# design.net
KiCad netlist of a schematic drawn in Altium Designer
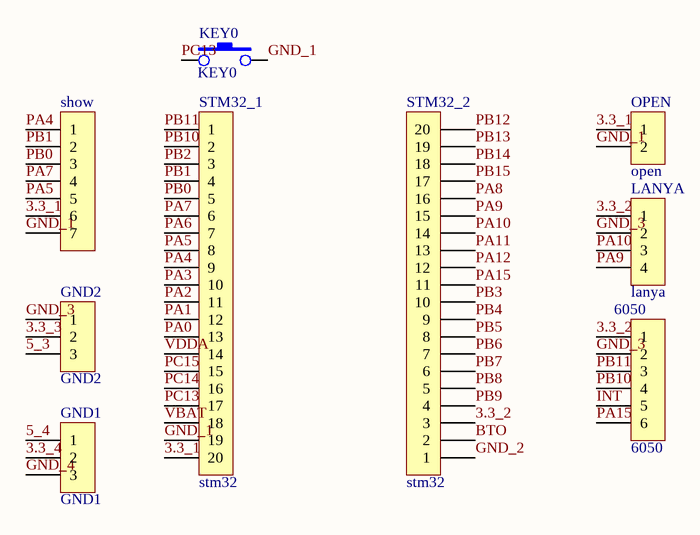
[diagram p0: 遥控器.SchDoc]

(export (version "E")
  (design (tool "Eeschema 10.0.6"))
  (components
    (comp (ref "6050")
      (value "6050")
      (footprint "Fe-HDR1X6/2.54-S")
      (libsource (lib "排母") (part "Female HDR1X6"))
    )
    (comp (ref "GND1")
      (value "GND1")
      (footprint "Fe-HDR1X3/2.54-S")
      (libsource (lib "排母") (part "Female HDR1X3"))
    )
    (comp (ref "GND2")
      (value "GND2")
      (footprint "Fe-HDR1X3/2.54-S")
      (libsource (lib "排母") (part "Female HDR1X3"))
    )
    (comp (ref "KEY0") (value "KEY0") (footprint "DIP-6X6X10") (libsource (lib "轻触开关") (part "KEY")))
    (comp (ref "LANYA")
      (value "lanya")
      (footprint "Fe-HDR1X4/2.54-S")
      (libsource (lib "排母") (part "Female HDR1X4"))
    )
    (comp (ref "OPEN")
      (value "open")
      (footprint "Pin HDR1X2/2.54mm-S")
      (libsource (lib "排针") (part "Pin HDR1X2"))
    )
    (comp (ref "show")
      (value "~")
      (footprint "Fe-HDR1X7/2.54-S")
      (libsource (lib "排母") (part "Female HDR1X7"))
    )
    (comp (ref "STM32_1")
      (value "stm32")
      (footprint "Fe-HDR1X20/2.54-S")
      (libsource (lib "") (part "Female HDR1X20_1"))
    )
    (comp (ref "STM32_2")
      (value "stm32")
      (footprint "Fe-HDR1X20/2.54-S")
      (libsource (lib "排母") (part "Female HDR1X20"))
    )
  )
  (nets
    (net (code "1") (name "/3.3_1") (class "Default")
      (node (ref "OPEN") (pin "1") (pinfunction "1_1") (pintype "passive"))
      (node (ref "STM32_1") (pin "20") (pinfunction "20_20") (pintype "passive"))
      (node (ref "show") (pin "6") (pinfunction "6_6") (pintype "passive"))
    )
    (net (code "2") (name "/3.3_2") (class "Default")
      (node (ref "6050") (pin "1") (pinfunction "1_1") (pintype "passive"))
      (node (ref "LANYA") (pin "1") (pinfunction "1_1") (pintype "passive"))
      (node (ref "STM32_2") (pin "3") (pinfunction "3_3") (pintype "passive"))
    )
    (net (code "3") (name "/3.3_3") (class "Default")
      (node (ref "GND2") (pin "2") (pinfunction "2_2") (pintype "passive"))
    )
    (net (code "4") (name "/3.3_4") (class "Default")
      (node (ref "GND1") (pin "2") (pinfunction "2_2") (pintype "passive"))
    )
    (net (code "5") (name "/5_3") (class "Default")
      (node (ref "GND2") (pin "3") (pinfunction "3_3") (pintype "passive"))
    )
    (net (code "6") (name "/5_4") (class "Default")
      (node (ref "GND1") (pin "1") (pinfunction "1_1") (pintype "passive"))
    )
    (net (code "7") (name "/BTO") (class "Default")
      (node (ref "STM32_2") (pin "2") (pinfunction "2_2") (pintype "passive"))
    )
    (net (code "8") (name "/GND_1") (class "Default")
      (node (ref "KEY0") (pin "3") (pinfunction "3_3") (pintype "passive"))
      (node (ref "OPEN") (pin "2") (pinfunction "2_2") (pintype "passive"))
      (node (ref "STM32_1") (pin "19") (pinfunction "19_19") (pintype "passive"))
      (node (ref "show") (pin "7") (pinfunction "7_7") (pintype "passive"))
    )
    (net (code "9") (name "/GND_2") (class "Default")
      (node (ref "STM32_2") (pin "1") (pinfunction "1_1") (pintype "passive"))
    )
    (net (code "10") (name "/GND_3") (class "Default")
      (node (ref "6050") (pin "2") (pinfunction "2_2") (pintype "passive"))
      (node (ref "GND2") (pin "1") (pinfunction "1_1") (pintype "passive"))
      (node (ref "LANYA") (pin "2") (pinfunction "2_2") (pintype "passive"))
    )
    (net (code "11") (name "/GND_4") (class "Default")
      (node (ref "GND1") (pin "3") (pinfunction "3_3") (pintype "passive"))
    )
    (net (code "12") (name "/INT") (class "Default")
      (node (ref "6050") (pin "5") (pinfunction "5_5") (pintype "passive"))
    )
    (net (code "13") (name "/PA0") (class "Default")
      (node (ref "STM32_1") (pin "13") (pinfunction "13_13") (pintype "passive"))
    )
    (net (code "14") (name "/PA1") (class "Default")
      (node (ref "STM32_1") (pin "12") (pinfunction "12_12") (pintype "passive"))
    )
    (net (code "15") (name "/PA2") (class "Default")
      (node (ref "STM32_1") (pin "11") (pinfunction "11_11") (pintype "passive"))
    )
    (net (code "16") (name "/PA3") (class "Default")
      (node (ref "STM32_1") (pin "10") (pinfunction "10_10") (pintype "passive"))
    )
    (net (code "17") (name "/PA4") (class "Default")
      (node (ref "STM32_1") (pin "9") (pinfunction "9_9") (pintype "passive"))
      (node (ref "show") (pin "1") (pinfunction "1_1") (pintype "passive"))
    )
    (net (code "18") (name "/PA5") (class "Default")
      (node (ref "STM32_1") (pin "8") (pinfunction "8_8") (pintype "passive"))
      (node (ref "show") (pin "5") (pinfunction "5_5") (pintype "passive"))
    )
    (net (code "19") (name "/PA6") (class "Default")
      (node (ref "STM32_1") (pin "7") (pinfunction "7_7") (pintype "passive"))
    )
    (net (code "20") (name "/PA7") (class "Default")
      (node (ref "STM32_1") (pin "6") (pinfunction "6_6") (pintype "passive"))
      (node (ref "show") (pin "4") (pinfunction "4_4") (pintype "passive"))
    )
    (net (code "21") (name "/PA8") (class "Default")
      (node (ref "STM32_2") (pin "16") (pinfunction "16_16") (pintype "passive"))
    )
    (net (code "22") (name "/PA9") (class "Default")
      (node (ref "LANYA") (pin "4") (pinfunction "4_4") (pintype "passive"))
      (node (ref "STM32_2") (pin "15") (pinfunction "15_15") (pintype "passive"))
    )
    (net (code "23") (name "/PA10") (class "Default")
      (node (ref "LANYA") (pin "3") (pinfunction "3_3") (pintype "passive"))
      (node (ref "STM32_2") (pin "14") (pinfunction "14_14") (pintype "passive"))
    )
    (net (code "24") (name "/PA11") (class "Default")
      (node (ref "STM32_2") (pin "13") (pinfunction "13_13") (pintype "passive"))
    )
    (net (code "25") (name "/PA12") (class "Default")
      (node (ref "STM32_2") (pin "12") (pinfunction "12_12") (pintype "passive"))
    )
    (net (code "26") (name "/PA15") (class "Default")
      (node (ref "6050") (pin "6") (pinfunction "6_6") (pintype "passive"))
      (node (ref "STM32_2") (pin "11") (pinfunction "11_11") (pintype "passive"))
    )
    (net (code "27") (name "/PB0") (class "Default")
      (node (ref "STM32_1") (pin "5") (pinfunction "5_5") (pintype "passive"))
      (node (ref "show") (pin "3") (pinfunction "3_3") (pintype "passive"))
    )
    (net (code "28") (name "/PB1") (class "Default")
      (node (ref "STM32_1") (pin "4") (pinfunction "4_4") (pintype "passive"))
      (node (ref "show") (pin "2") (pinfunction "2_2") (pintype "passive"))
    )
    (net (code "29") (name "/PB2") (class "Default")
      (node (ref "STM32_1") (pin "3") (pinfunction "3_3") (pintype "passive"))
    )
    (net (code "30") (name "/PB3") (class "Default")
      (node (ref "STM32_2") (pin "10") (pinfunction "10_10") (pintype "passive"))
    )
    (net (code "31") (name "/PB4") (class "Default")
      (node (ref "STM32_2") (pin "9") (pinfunction "9_9") (pintype "passive"))
    )
    (net (code "32") (name "/PB5") (class "Default")
      (node (ref "STM32_2") (pin "8") (pinfunction "8_8") (pintype "passive"))
    )
    (net (code "33") (name "/PB6") (class "Default")
      (node (ref "STM32_2") (pin "7") (pinfunction "7_7") (pintype "passive"))
    )
    (net (code "34") (name "/PB7") (class "Default")
      (node (ref "STM32_2") (pin "6") (pinfunction "6_6") (pintype "passive"))
    )
    (net (code "35") (name "/PB8") (class "Default")
      (node (ref "STM32_2") (pin "5") (pinfunction "5_5") (pintype "passive"))
    )
    (net (code "36") (name "/PB9") (class "Default")
      (node (ref "STM32_2") (pin "4") (pinfunction "4_4") (pintype "passive"))
    )
    (net (code "37") (name "/PB10") (class "Default")
      (node (ref "6050") (pin "4") (pinfunction "4_4") (pintype "passive"))
      (node (ref "STM32_1") (pin "2") (pinfunction "2_2") (pintype "passive"))
    )
    (net (code "38") (name "/PB11") (class "Default")
      (node (ref "6050") (pin "3") (pinfunction "3_3") (pintype "passive"))
      (node (ref "STM32_1") (pin "1") (pinfunction "1_1") (pintype "passive"))
    )
    (net (code "39") (name "/PB12") (class "Default")
      (node (ref "STM32_2") (pin "20") (pinfunction "20_20") (pintype "passive"))
    )
    (net (code "40") (name "/PB13") (class "Default")
      (node (ref "STM32_2") (pin "19") (pinfunction "19_19") (pintype "passive"))
    )
    (net (code "41") (name "/PB14") (class "Default")
      (node (ref "STM32_2") (pin "18") (pinfunction "18_18") (pintype "passive"))
    )
    (net (code "42") (name "/PB15") (class "Default")
      (node (ref "STM32_2") (pin "17") (pinfunction "17_17") (pintype "passive"))
    )
    (net (code "43") (name "/PC13") (class "Default")
      (node (ref "KEY0") (pin "1") (pinfunction "1_1") (pintype "passive"))
      (node (ref "STM32_1") (pin "17") (pinfunction "17_17") (pintype "passive"))
    )
    (net (code "44") (name "/PC14") (class "Default")
      (node (ref "STM32_1") (pin "16") (pinfunction "16_16") (pintype "passive"))
    )
    (net (code "45") (name "/PC15") (class "Default")
      (node (ref "STM32_1") (pin "15") (pinfunction "15_15") (pintype "passive"))
    )
    (net (code "46") (name "/VBAT") (class "Default")
      (node (ref "STM32_1") (pin "18") (pinfunction "18_18") (pintype "passive"))
    )
    (net (code "47") (name "/VDDA") (class "Default")
      (node (ref "STM32_1") (pin "14") (pinfunction "14_14") (pintype "passive"))
    )
  )
)
